# Low_Pass_Filter_Ing_Galilee.net
KiCad netlist of a schematic drawn in Altium Designer
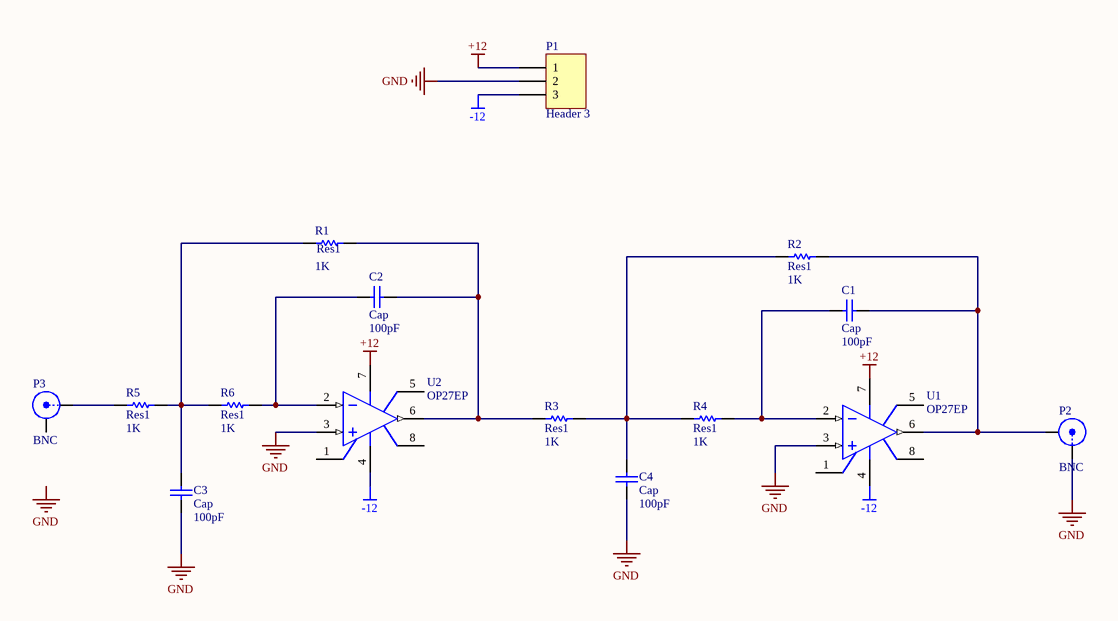
[diagram p0: Low_Pass_Filter_Ing_Galilee.SchDoc]

(export (version "E")
  (design (tool "Eeschema 10.0.6"))
  (components
    (comp (ref "C1")
      (value "Cap")
      (footprint "RAD-0.3")
      (description "Capacitor")
      (fields (field (name "ALTIUM_VALUE") "100pF") (field (name "PUBLISHER") "Altium Limited"))
      (libsource (lib "Miscellaneous Devices") (part "Cap"))
    )
    (comp (ref "C2")
      (value "Cap")
      (footprint "RAD-0.3")
      (description "Capacitor")
      (fields (field (name "ALTIUM_VALUE") "100pF") (field (name "PUBLISHER") "Altium Limited"))
      (libsource (lib "Miscellaneous Devices") (part "Cap"))
    )
    (comp (ref "C3")
      (value "Cap")
      (footprint "RAD-0.3")
      (description "Capacitor")
      (fields (field (name "ALTIUM_VALUE") "100pF") (field (name "PUBLISHER") "Altium Limited"))
      (libsource (lib "Miscellaneous Devices") (part "Cap"))
    )
    (comp (ref "C4")
      (value "Cap")
      (footprint "RAD-0.3")
      (description "Capacitor")
      (fields (field (name "ALTIUM_VALUE") "100pF") (field (name "PUBLISHER") "Altium Limited"))
      (libsource (lib "Miscellaneous Devices") (part "Cap"))
    )
    (comp (ref "P1")
      (value "Header 3")
      (footprint "HDR1X3")
      (description "Header, 3-Pin")
      (fields (field (name "PUBLISHER") "Altium Limited"))
      (libsource (lib "Miscellaneous Connectors") (part "Header 3"))
    )
    (comp (ref "P2")
      (value "BNC")
      (footprint "BNC_RA CON")
      (description "BNC Elbow Connector")
      (fields (field (name "PUBLISHER") "Altium Limited"))
      (libsource (lib "Miscellaneous Connectors") (part "BNC"))
    )
    (comp (ref "P3")
      (value "BNC")
      (footprint "BNC_RA CON")
      (description "BNC Elbow Connector")
      (fields (field (name "PUBLISHER") "Altium Limited"))
      (libsource (lib "Miscellaneous Connectors") (part "BNC"))
    )
    (comp (ref "R1")
      (value "Res1")
      (footprint "AXIAL-0.3")
      (description "Resistor")
      (fields (field (name "ALTIUM_VALUE") "1K") (field (name "PUBLISHER") "Altium Limited"))
      (libsource (lib "Miscellaneous Devices") (part "Res1"))
    )
    (comp (ref "R2")
      (value "Res1")
      (footprint "AXIAL-0.3")
      (description "Resistor")
      (fields (field (name "ALTIUM_VALUE") "1K") (field (name "PUBLISHER") "Altium Limited"))
      (libsource (lib "Miscellaneous Devices") (part "Res1"))
    )
    (comp (ref "R3")
      (value "Res1")
      (footprint "AXIAL-0.3")
      (description "Resistor")
      (fields (field (name "ALTIUM_VALUE") "1K") (field (name "PUBLISHER") "Altium Limited"))
      (libsource (lib "Miscellaneous Devices") (part "Res1"))
    )
    (comp (ref "R4")
      (value "Res1")
      (footprint "AXIAL-0.3")
      (description "Resistor")
      (fields (field (name "ALTIUM_VALUE") "1K") (field (name "PUBLISHER") "Altium Limited"))
      (libsource (lib "Miscellaneous Devices") (part "Res1"))
    )
    (comp (ref "R5")
      (value "Res1")
      (footprint "AXIAL-0.3")
      (description "Resistor")
      (fields (field (name "ALTIUM_VALUE") "1K") (field (name "PUBLISHER") "Altium Limited"))
      (libsource (lib "Miscellaneous Devices") (part "Res1"))
    )
    (comp (ref "R6")
      (value "Res1")
      (footprint "AXIAL-0.3")
      (description "Resistor")
      (fields (field (name "ALTIUM_VALUE") "1K") (field (name "PUBLISHER") "Altium Limited"))
      (libsource (lib "Miscellaneous Devices") (part "Res1"))
    )
    (comp (ref "U1")
      (value "OP27EP")
      (footprint "N-8_A")
      (description "Low-Noise, Precision Operational Amplifier")
      (fields (field (name "PUBLISHER") "Altium Limited"))
      (libsource (lib "AD Operational Amplifier") (part "OP27EP"))
    )
    (comp (ref "U2")
      (value "OP27EP")
      (footprint "N-8_A")
      (description "Low-Noise, Precision Operational Amplifier")
      (fields (field (name "PUBLISHER") "Altium Limited"))
      (libsource (lib "AD Operational Amplifier") (part "OP27EP"))
    )
  )
  (nets
    (net (code "1") (name "+12") (class "Default")
      (node (ref "P1") (pin "1") (pinfunction "1_1") (pintype "passive"))
      (node (ref "U1") (pin "7") (pinfunction "V+_7") (pintype "power_in"))
      (node (ref "U2") (pin "7") (pinfunction "V+_7") (pintype "power_in"))
    )
    (net (code "2") (name "-12") (class "Default")
      (node (ref "P1") (pin "3") (pinfunction "3_3") (pintype "passive"))
      (node (ref "U1") (pin "4") (pinfunction "V-_4") (pintype "power_in"))
      (node (ref "U2") (pin "4") (pinfunction "V-_4") (pintype "power_in"))
    )
    (net (code "3") (name "GND") (class "Default")
      (node (ref "C3") (pin "1") (pinfunction "1_1") (pintype "passive"))
      (node (ref "C4") (pin "1") (pinfunction "1_1") (pintype "passive"))
      (node (ref "P1") (pin "2") (pinfunction "2_2") (pintype "passive"))
      (node (ref "P2") (pin "1") (pinfunction "X_1") (pintype "passive"))
      (node (ref "U1") (pin "3") (pinfunction "IN+_3") (pintype "input"))
      (node (ref "U2") (pin "3") (pinfunction "IN+_3") (pintype "input"))
    )
    (net (code "4") (name "Net-(C3-Pad2)") (class "Default")
      (node (ref "C3") (pin "2") (pinfunction "2_2") (pintype "passive"))
      (node (ref "R1") (pin "1") (pinfunction "1_1") (pintype "passive"))
      (node (ref "R5") (pin "2") (pinfunction "2_2") (pintype "passive"))
      (node (ref "R6") (pin "1") (pinfunction "1_1") (pintype "passive"))
    )
    (net (code "5") (name "Net-(C4-Pad2)") (class "Default")
      (node (ref "C4") (pin "2") (pinfunction "2_2") (pintype "passive"))
      (node (ref "R2") (pin "1") (pinfunction "1_1") (pintype "passive"))
      (node (ref "R3") (pin "2") (pinfunction "2_2") (pintype "passive"))
      (node (ref "R4") (pin "1") (pinfunction "1_1") (pintype "passive"))
    )
    (net (code "6") (name "Net-(P2-Y)") (class "Default")
      (node (ref "C1") (pin "1") (pinfunction "1_1") (pintype "passive"))
      (node (ref "P2") (pin "2") (pinfunction "Y_2") (pintype "passive"))
      (node (ref "R2") (pin "2") (pinfunction "2_2") (pintype "passive"))
      (node (ref "U1") (pin "6") (pinfunction "OUT_6") (pintype "output"))
    )
    (net (code "7") (name "Net-(P3-X)") (class "Default")
      (node (ref "P3") (pin "1") (pinfunction "X_1") (pintype "passive"))
      (node (ref "R5") (pin "1") (pinfunction "1_1") (pintype "passive"))
    )
    (net (code "8") (name "Net-(U1-IN-)") (class "Default")
      (node (ref "C1") (pin "2") (pinfunction "2_2") (pintype "passive"))
      (node (ref "R4") (pin "2") (pinfunction "2_2") (pintype "passive"))
      (node (ref "U1") (pin "2") (pinfunction "IN-_2") (pintype "input"))
    )
    (net (code "9") (name "Net-(U2-IN-)") (class "Default")
      (node (ref "C2") (pin "2") (pinfunction "2_2") (pintype "passive"))
      (node (ref "R6") (pin "2") (pinfunction "2_2") (pintype "passive"))
      (node (ref "U2") (pin "2") (pinfunction "IN-_2") (pintype "input"))
    )
    (net (code "10") (name "Net-(U2-OUT)") (class "Default")
      (node (ref "C2") (pin "1") (pinfunction "1_1") (pintype "passive"))
      (node (ref "R1") (pin "2") (pinfunction "2_2") (pintype "passive"))
      (node (ref "R3") (pin "1") (pinfunction "1_1") (pintype "passive"))
      (node (ref "U2") (pin "6") (pinfunction "OUT_6") (pintype "output"))
    )
    (net (code "11") (name "unconnected-(P3-Y-Pad2)") (class "Default")
      (node (ref "P3") (pin "2") (pinfunction "Y_2") (pintype "passive"))
    )
    (net (code "12") (name "unconnected-(U1-CMPEN-Pad1)") (class "Default")
      (node (ref "U1") (pin "1") (pinfunction "CMPEN_1") (pintype "passive"))
    )
    (net (code "13") (name "unconnected-(U1-CMPEN-Pad8)") (class "Default")
      (node (ref "U1") (pin "8") (pinfunction "CMPEN_8") (pintype "passive"))
    )
    (net (code "14") (name "unconnected-(U1-NC-Pad5)") (class "Default")
      (node (ref "U1") (pin "5") (pinfunction "NC_5") (pintype "passive"))
    )
    (net (code "15") (name "unconnected-(U2-CMPEN-Pad1)") (class "Default")
      (node (ref "U2") (pin "1") (pinfunction "CMPEN_1") (pintype "passive"))
    )
    (net (code "16") (name "unconnected-(U2-CMPEN-Pad8)") (class "Default")
      (node (ref "U2") (pin "8") (pinfunction "CMPEN_8") (pintype "passive"))
    )
    (net (code "17") (name "unconnected-(U2-NC-Pad5)") (class "Default")
      (node (ref "U2") (pin "5") (pinfunction "NC_5") (pintype "passive"))
    )
  )
)
